# esp32c3-devboard.net
KiCad netlist of a schematic drawn in EAGLE
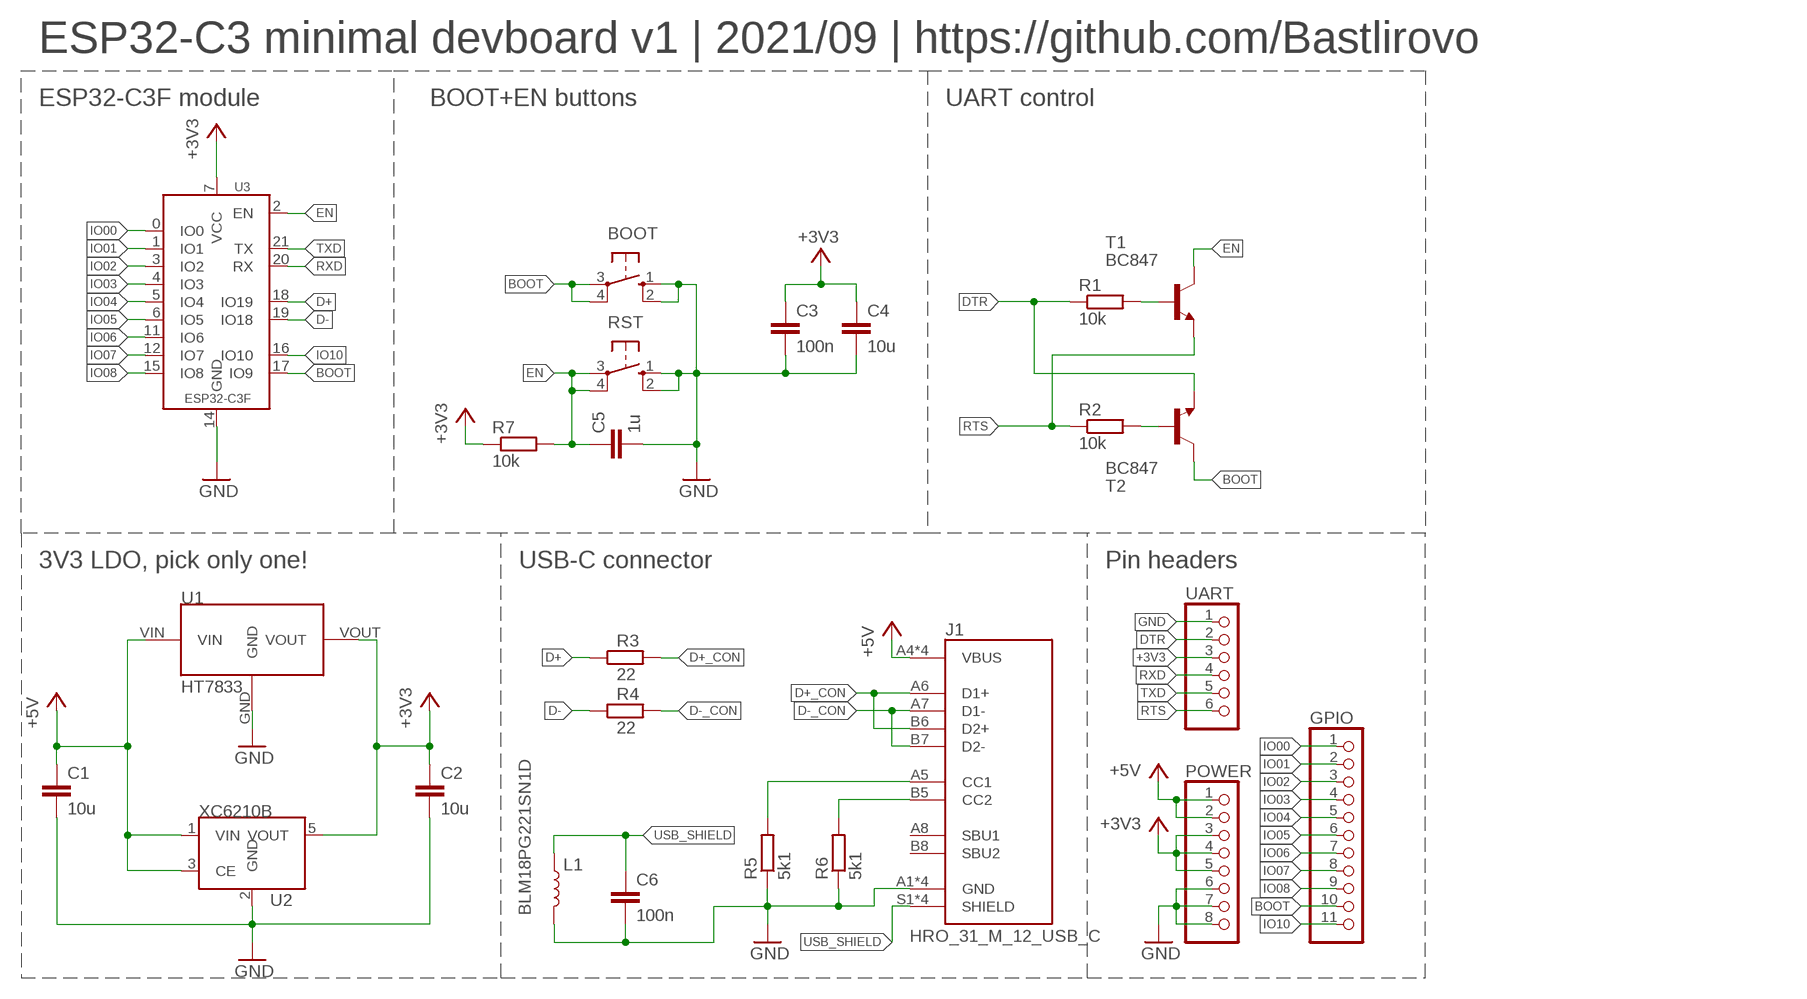
[diagram p0: schematic, sheet 1]

(export (version "E")
  (design (tool "Eeschema 10.0.6"))
  (components
    (comp (ref "BOOT")
      (value "10-XX")
      (footprint "eagle-import:B3F-10XX")
      (fields (field (name "MPN") "B3F-1000"))
      (libsource (lib "eagle-import") (part "10-XX"))
    )
    (comp (ref "C1")
      (value "10u")
      (footprint "eagle-import:C0603")
      (libsource (lib "eagle-import") (part "C-EUC0603"))
    )
    (comp (ref "C2")
      (value "10u")
      (footprint "eagle-import:C0603")
      (libsource (lib "eagle-import") (part "C-EUC0603"))
    )
    (comp (ref "C3")
      (value "100n")
      (footprint "eagle-import:C0603")
      (libsource (lib "eagle-import") (part "C-EUC0603"))
    )
    (comp (ref "C4")
      (value "10u")
      (footprint "eagle-import:C0603")
      (libsource (lib "eagle-import") (part "C-EUC0603"))
    )
    (comp (ref "C5")
      (value "1u")
      (footprint "eagle-import:C0603")
      (libsource (lib "eagle-import") (part "C-EUC0603"))
    )
    (comp (ref "C6")
      (value "100n")
      (footprint "eagle-import:C0603")
      (libsource (lib "eagle-import") (part "C-EUC0603"))
    )
    (comp (ref "GPIO")
      (value "PINHD-1X11")
      (footprint "eagle-import:1X11")
      (libsource (lib "eagle-import") (part "PINHD-1X11"))
    )
    (comp (ref "J1")
      (value "HRO_31_M_12_USB_C")
      (footprint "eagle-import:HRO_31_M_12_USB_C")
      (libsource (lib "eagle-import") (part "HRO_31_M_12_USB_C"))
    )
    (comp (ref "L1")
      (value "BLM18PG221SN1D")
      (footprint "eagle-import:0603")
      (libsource (lib "eagle-import") (part "INDUCTOR-0603-33NH"))
    )
    (comp (ref "POWER")
      (value "PINHD-1X8")
      (footprint "eagle-import:1X08")
      (libsource (lib "eagle-import") (part "PINHD-1X8"))
    )
    (comp (ref "R1")
      (value "10k")
      (footprint "eagle-import:R0603")
      (libsource (lib "eagle-import") (part "R-EU_R0603"))
    )
    (comp (ref "R2")
      (value "10k")
      (footprint "eagle-import:R0603")
      (libsource (lib "eagle-import") (part "R-EU_R0603"))
    )
    (comp (ref "R3")
      (value "22")
      (footprint "eagle-import:R0603")
      (libsource (lib "eagle-import") (part "R-EU_R0603"))
    )
    (comp (ref "R4")
      (value "22")
      (footprint "eagle-import:R0603")
      (libsource (lib "eagle-import") (part "R-EU_R0603"))
    )
    (comp (ref "R5")
      (value "5k1")
      (footprint "eagle-import:R0603")
      (libsource (lib "eagle-import") (part "R-EU_R0603"))
    )
    (comp (ref "R6")
      (value "5k1")
      (footprint "eagle-import:R0603")
      (libsource (lib "eagle-import") (part "R-EU_R0603"))
    )
    (comp (ref "R7")
      (value "10k")
      (footprint "eagle-import:R0603")
      (libsource (lib "eagle-import") (part "R-EU_R0603"))
    )
    (comp (ref "RST")
      (value "10-XX")
      (footprint "eagle-import:B3F-10XX")
      (fields (field (name "MPN") "B3F-1000"))
      (libsource (lib "eagle-import") (part "10-XX"))
    )
    (comp (ref "T1")
      (value "BC847")
      (footprint "eagle-import:SOT23")
      (libsource (lib "eagle-import") (part "BC847"))
    )
    (comp (ref "T2")
      (value "BC847")
      (footprint "eagle-import:SOT23")
      (libsource (lib "eagle-import") (part "BC847"))
    )
    (comp (ref "U1")
      (value "HT7833")
      (footprint "eagle-import:SOT89")
      (libsource (lib "eagle-import") (part "HT7833"))
    )
    (comp (ref "U2")
      (value "XC6210")
      (footprint "eagle-import:SOT-23-5")
      (libsource (lib "eagle-import") (part "XC6210"))
    )
    (comp (ref "U3")
      (value "ESP32-C3F")
      (footprint "eagle-import:ESP32-C3F")
      (libsource (lib "eagle-import") (part "ESP32-C3F"))
    )
    (comp (ref "UART")
      (value "PINHD-1X6")
      (footprint "eagle-import:1X06")
      (libsource (lib "eagle-import") (part "PINHD-1X6"))
    )
  )
  (nets
    (net (code "1") (name "+3V3") (class "Default")
      (node (ref "C2") (pin "1") (pinfunction "1_1") (pintype "passive"))
      (node (ref "C3") (pin "1") (pinfunction "1_1") (pintype "passive"))
      (node (ref "C4") (pin "1") (pinfunction "1_1") (pintype "passive"))
      (node (ref "POWER") (pin "3") (pinfunction "3_3") (pintype "passive"))
      (node (ref "POWER") (pin "4") (pinfunction "4_4") (pintype "passive"))
      (node (ref "POWER") (pin "5") (pinfunction "5_5") (pintype "passive"))
      (node (ref "R7") (pin "1") (pinfunction "1_1") (pintype "passive"))
      (node (ref "U1") (pin "VOUT") (pinfunction "VOUT_VOUT") (pintype "bidirectional"))
      (node (ref "U2") (pin "5") (pinfunction "VOUT_5") (pintype "power_in"))
      (node (ref "U3") (pin "7") (pinfunction "VCC_7") (pintype "power_in"))
      (node (ref "UART") (pin "3") (pinfunction "3_3") (pintype "passive"))
    )
    (net (code "2") (name "+5V") (class "Default")
      (node (ref "C1") (pin "1") (pinfunction "1_1") (pintype "passive"))
      (node (ref "J1") (pin "A4") (pinfunction "VBUS_A4") (pintype "passive"))
      (node (ref "J1") (pin "A9") (pinfunction "VBUS_A9") (pintype "passive"))
      (node (ref "J1") (pin "B4") (pinfunction "VBUS_B4") (pintype "passive"))
      (node (ref "J1") (pin "B9") (pinfunction "VBUS_B9") (pintype "passive"))
      (node (ref "POWER") (pin "1") (pinfunction "1_1") (pintype "passive"))
      (node (ref "POWER") (pin "2") (pinfunction "2_2") (pintype "passive"))
      (node (ref "U1") (pin "VIN") (pinfunction "VIN_VIN") (pintype "bidirectional"))
      (node (ref "U2") (pin "1") (pinfunction "VIN_1") (pintype "power_in"))
      (node (ref "U2") (pin "3") (pinfunction "CE_3") (pintype "power_in"))
    )
    (net (code "3") (name "BOOT") (class "Default")
      (node (ref "BOOT") (pin "3") (pinfunction "P_3") (pintype "passive"))
      (node (ref "BOOT") (pin "4") (pinfunction "P1_4") (pintype "passive"))
      (node (ref "GPIO") (pin "10") (pinfunction "10_10") (pintype "passive"))
      (node (ref "T2") (pin "3") (pinfunction "C_3") (pintype "passive"))
      (node (ref "U3") (pin "17") (pinfunction "IO9_17") (pintype "bidirectional"))
    )
    (net (code "4") (name "D+") (class "Default")
      (node (ref "R3") (pin "1") (pinfunction "1_1") (pintype "passive"))
      (node (ref "U3") (pin "18") (pinfunction "IO19_18") (pintype "bidirectional"))
    )
    (net (code "5") (name "D+_CON") (class "Default")
      (node (ref "J1") (pin "A6") (pinfunction "D1+_A6") (pintype "passive"))
      (node (ref "J1") (pin "B6") (pinfunction "D2+_B6") (pintype "passive"))
      (node (ref "R3") (pin "2") (pinfunction "2_2") (pintype "passive"))
    )
    (net (code "6") (name "D-") (class "Default")
      (node (ref "R4") (pin "1") (pinfunction "1_1") (pintype "passive"))
      (node (ref "U3") (pin "19") (pinfunction "IO18_19") (pintype "bidirectional"))
    )
    (net (code "7") (name "D-_CON") (class "Default")
      (node (ref "J1") (pin "A7") (pinfunction "D1-_A7") (pintype "passive"))
      (node (ref "J1") (pin "B7") (pinfunction "D2-_B7") (pintype "passive"))
      (node (ref "R4") (pin "2") (pinfunction "2_2") (pintype "passive"))
    )
    (net (code "8") (name "DTR") (class "Default")
      (node (ref "R1") (pin "1") (pinfunction "1_1") (pintype "passive"))
      (node (ref "T2") (pin "2") (pinfunction "E_2") (pintype "passive"))
      (node (ref "UART") (pin "2") (pinfunction "2_2") (pintype "passive"))
    )
    (net (code "9") (name "EN") (class "Default")
      (node (ref "C5") (pin "1") (pinfunction "1_1") (pintype "passive"))
      (node (ref "R7") (pin "2") (pinfunction "2_2") (pintype "passive"))
      (node (ref "RST") (pin "3") (pinfunction "P_3") (pintype "passive"))
      (node (ref "RST") (pin "4") (pinfunction "P1_4") (pintype "passive"))
      (node (ref "T1") (pin "3") (pinfunction "C_3") (pintype "passive"))
      (node (ref "U3") (pin "2") (pinfunction "EN_2") (pintype "bidirectional"))
    )
    (net (code "10") (name "GND") (class "Default")
      (node (ref "BOOT") (pin "1") (pinfunction "S_1") (pintype "passive"))
      (node (ref "BOOT") (pin "2") (pinfunction "S1_2") (pintype "passive"))
      (node (ref "C1") (pin "2") (pinfunction "2_2") (pintype "passive"))
      (node (ref "C2") (pin "2") (pinfunction "2_2") (pintype "passive"))
      (node (ref "C3") (pin "2") (pinfunction "2_2") (pintype "passive"))
      (node (ref "C4") (pin "2") (pinfunction "2_2") (pintype "passive"))
      (node (ref "C5") (pin "2") (pinfunction "2_2") (pintype "passive"))
      (node (ref "C6") (pin "2") (pinfunction "2_2") (pintype "passive"))
      (node (ref "J1") (pin "A1") (pinfunction "GND_A1") (pintype "passive"))
      (node (ref "J1") (pin "A12") (pinfunction "GND_A12") (pintype "passive"))
      (node (ref "J1") (pin "B1") (pinfunction "GND_B1") (pintype "passive"))
      (node (ref "J1") (pin "B12") (pinfunction "GND_B12") (pintype "passive"))
      (node (ref "L1") (pin "2") (pinfunction "2_2") (pintype "passive"))
      (node (ref "POWER") (pin "6") (pinfunction "6_6") (pintype "passive"))
      (node (ref "POWER") (pin "7") (pinfunction "7_7") (pintype "passive"))
      (node (ref "POWER") (pin "8") (pinfunction "8_8") (pintype "passive"))
      (node (ref "R5") (pin "1") (pinfunction "1_1") (pintype "passive"))
      (node (ref "R6") (pin "1") (pinfunction "1_1") (pintype "passive"))
      (node (ref "RST") (pin "1") (pinfunction "S_1") (pintype "passive"))
      (node (ref "RST") (pin "2") (pinfunction "S1_2") (pintype "passive"))
      (node (ref "U1") (pin "GND") (pinfunction "GND_GND") (pintype "bidirectional"))
      (node (ref "U2") (pin "2") (pinfunction "GND_2") (pintype "power_in"))
      (node (ref "U3") (pin "14") (pinfunction "GND_14") (pintype "power_in"))
      (node (ref "UART") (pin "1") (pinfunction "1_1") (pintype "passive"))
    )
    (net (code "11") (name "IO00") (class "Default")
      (node (ref "GPIO") (pin "1") (pinfunction "1_1") (pintype "passive"))
      (node (ref "U3") (pin "0") (pinfunction "IO0_0") (pintype "bidirectional"))
    )
    (net (code "12") (name "IO01") (class "Default")
      (node (ref "GPIO") (pin "2") (pinfunction "2_2") (pintype "passive"))
      (node (ref "U3") (pin "1") (pinfunction "IO1_1") (pintype "bidirectional"))
    )
    (net (code "13") (name "IO02") (class "Default")
      (node (ref "GPIO") (pin "3") (pinfunction "3_3") (pintype "passive"))
      (node (ref "U3") (pin "3") (pinfunction "IO2_3") (pintype "bidirectional"))
    )
    (net (code "14") (name "IO03") (class "Default")
      (node (ref "GPIO") (pin "4") (pinfunction "4_4") (pintype "passive"))
      (node (ref "U3") (pin "4") (pinfunction "IO3_4") (pintype "bidirectional"))
    )
    (net (code "15") (name "IO04") (class "Default")
      (node (ref "GPIO") (pin "5") (pinfunction "5_5") (pintype "passive"))
      (node (ref "U3") (pin "5") (pinfunction "IO4_5") (pintype "bidirectional"))
    )
    (net (code "16") (name "IO05") (class "Default")
      (node (ref "GPIO") (pin "6") (pinfunction "6_6") (pintype "passive"))
      (node (ref "U3") (pin "6") (pinfunction "IO5_6") (pintype "bidirectional"))
    )
    (net (code "17") (name "IO06") (class "Default")
      (node (ref "GPIO") (pin "7") (pinfunction "7_7") (pintype "passive"))
      (node (ref "U3") (pin "11") (pinfunction "IO6_11") (pintype "bidirectional"))
    )
    (net (code "18") (name "IO07") (class "Default")
      (node (ref "GPIO") (pin "8") (pinfunction "8_8") (pintype "passive"))
      (node (ref "U3") (pin "12") (pinfunction "IO7_12") (pintype "bidirectional"))
    )
    (net (code "19") (name "IO08") (class "Default")
      (node (ref "GPIO") (pin "9") (pinfunction "9_9") (pintype "passive"))
      (node (ref "U3") (pin "15") (pinfunction "IO8_15") (pintype "bidirectional"))
    )
    (net (code "20") (name "IO10") (class "Default")
      (node (ref "GPIO") (pin "11") (pinfunction "11_11") (pintype "passive"))
      (node (ref "U3") (pin "16") (pinfunction "IO10_16") (pintype "bidirectional"))
    )
    (net (code "21") (name "Net-(J1-CC1)") (class "Default")
      (node (ref "J1") (pin "A5") (pinfunction "CC1_A5") (pintype "passive"))
      (node (ref "R5") (pin "2") (pinfunction "2_2") (pintype "passive"))
    )
    (net (code "22") (name "Net-(J1-CC2)") (class "Default")
      (node (ref "J1") (pin "B5") (pinfunction "CC2_B5") (pintype "passive"))
      (node (ref "R6") (pin "2") (pinfunction "2_2") (pintype "passive"))
    )
    (net (code "23") (name "Net-(T1-B)") (class "Default")
      (node (ref "R1") (pin "2") (pinfunction "2_2") (pintype "passive"))
      (node (ref "T1") (pin "1") (pinfunction "B_1") (pintype "passive"))
    )
    (net (code "24") (name "Net-(T2-B)") (class "Default")
      (node (ref "R2") (pin "2") (pinfunction "2_2") (pintype "passive"))
      (node (ref "T2") (pin "1") (pinfunction "B_1") (pintype "passive"))
    )
    (net (code "25") (name "RTS") (class "Default")
      (node (ref "R2") (pin "1") (pinfunction "1_1") (pintype "passive"))
      (node (ref "T1") (pin "2") (pinfunction "E_2") (pintype "passive"))
      (node (ref "UART") (pin "6") (pinfunction "6_6") (pintype "passive"))
    )
    (net (code "26") (name "RXD") (class "Default")
      (node (ref "U3") (pin "20") (pinfunction "RX_20") (pintype "bidirectional"))
      (node (ref "UART") (pin "4") (pinfunction "4_4") (pintype "passive"))
    )
    (net (code "27") (name "TXD") (class "Default")
      (node (ref "U3") (pin "21") (pinfunction "TX_21") (pintype "bidirectional"))
      (node (ref "UART") (pin "5") (pinfunction "5_5") (pintype "passive"))
    )
    (net (code "28") (name "USB_SHIELD") (class "Default")
      (node (ref "C6") (pin "1") (pinfunction "1_1") (pintype "passive"))
      (node (ref "J1") (pin "S1") (pinfunction "SHIELD_S1") (pintype "passive"))
      (node (ref "J1") (pin "S2") (pinfunction "SHIELD_S2") (pintype "passive"))
      (node (ref "J1") (pin "S3") (pinfunction "SHIELD_S3") (pintype "passive"))
      (node (ref "J1") (pin "S4") (pinfunction "SHIELD_S4") (pintype "passive"))
      (node (ref "L1") (pin "1") (pinfunction "1_1") (pintype "passive"))
    )
    (net (code "29") (name "unconnected-(J1-SBU1-PadA8)") (class "Default")
      (node (ref "J1") (pin "A8") (pinfunction "SBU1_A8") (pintype "passive"))
    )
    (net (code "30") (name "unconnected-(J1-SBU2-PadB8)") (class "Default")
      (node (ref "J1") (pin "B8") (pinfunction "SBU2_B8") (pintype "passive"))
    )
  )
)
